# INTERPLACA.net
KiCad netlist of a schematic drawn in Altium Designer
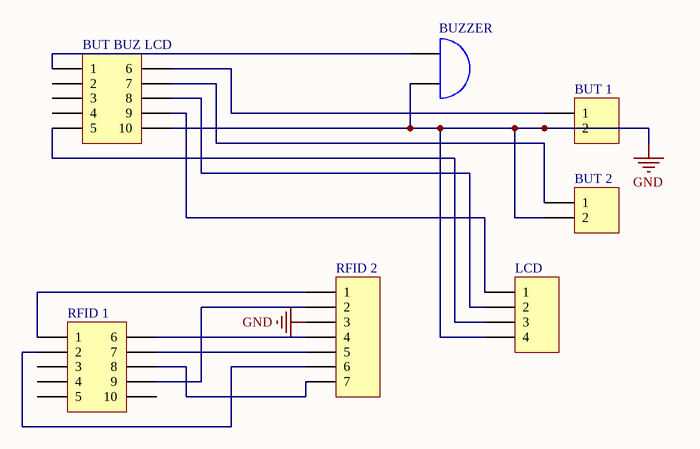
[diagram p0: INTERPLACA.SchDoc]

(export (version "E")
  (design (tool "Eeschema 10.0.6"))
  (components
    (comp (ref "BUT 1")
      (value "Header 2")
      (footprint "BORNERA 2 pin")
      (description "Header, 2-Pin")
      (fields (field (name "PUBLISHER") "Altium Limited"))
      (libsource (lib "Miscellaneous Connectors") (part "Header 2"))
    )
    (comp (ref "BUT 2")
      (value "Header 2")
      (footprint "BORNERA 2 pin")
      (description "Header, 2-Pin")
      (fields (field (name "PUBLISHER") "Altium Limited"))
      (libsource (lib "Miscellaneous Connectors") (part "Header 2"))
    )
    (comp (ref "BUT BUZ LCD")
      (value "Header 5X2A")
      (footprint "HDR2X5_CEN")
      (description "Header, 5-Pin, Dual row")
      (fields (field (name "PUBLISHER") "Altium Limited"))
      (libsource (lib "Miscellaneous Connectors") (part "Header 5X2A"))
    )
    (comp (ref "BUZZER")
      (value "Bell")
      (footprint "PIN2")
      (description "Electrical Bell")
      (fields (field (name "PUBLISHER") "Altium Limited"))
      (libsource (lib "Miscellaneous Devices") (part "Bell"))
    )
    (comp (ref "LCD")
      (value "Header 4")
      (footprint "HDR1X4")
      (description "Header, 4-Pin")
      (fields (field (name "PUBLISHER") "Altium Limited"))
      (libsource (lib "Miscellaneous Connectors") (part "Header 4"))
    )
    (comp (ref "RFID 1")
      (value "Header 5X2A")
      (footprint "HDR2X5_CEN")
      (description "Header, 5-Pin, Dual row")
      (fields (field (name "PUBLISHER") "Altium Limited"))
      (libsource (lib "Miscellaneous Connectors") (part "Header 5X2A"))
    )
    (comp (ref "RFID 2")
      (value "Header 7")
      (footprint "HDR1X7")
      (description "Header, 7-Pin")
      (fields (field (name "PUBLISHER") "Altium Limited"))
      (libsource (lib "Miscellaneous Connectors") (part "Header 7"))
    )
  )
  (nets
    (net (code "1") (name "GND") (class "Default")
      (node (ref "BUT 1") (pin "2") (pinfunction "2_2") (pintype "passive"))
      (node (ref "BUT 2") (pin "2") (pinfunction "2_2") (pintype "passive"))
      (node (ref "BUT BUZ LCD") (pin "10") (pinfunction "10_10") (pintype "passive"))
      (node (ref "BUZZER") (pin "2") (pinfunction "B_2") (pintype "passive"))
      (node (ref "LCD") (pin "4") (pinfunction "4_4") (pintype "passive"))
      (node (ref "RFID 2") (pin "3") (pinfunction "3_3") (pintype "passive"))
    )
    (net (code "2") (name "Net-(BUT 1-Pad1)") (class "Default")
      (node (ref "BUT 1") (pin "1") (pinfunction "1_1") (pintype "passive"))
      (node (ref "BUT BUZ LCD") (pin "6") (pinfunction "6_6") (pintype "passive"))
    )
    (net (code "3") (name "Net-(BUT 2-Pad1)") (class "Default")
      (node (ref "BUT 2") (pin "1") (pinfunction "1_1") (pintype "passive"))
      (node (ref "BUT BUZ LCD") (pin "7") (pinfunction "7_7") (pintype "passive"))
    )
    (net (code "4") (name "Net-(BUT BUZ LCD-Pad5)") (class "Default")
      (node (ref "BUT BUZ LCD") (pin "5") (pinfunction "5_5") (pintype "passive"))
      (node (ref "LCD") (pin "3") (pinfunction "3_3") (pintype "passive"))
    )
    (net (code "5") (name "Net-(BUT BUZ LCD-Pad8)") (class "Default")
      (node (ref "BUT BUZ LCD") (pin "8") (pinfunction "8_8") (pintype "passive"))
      (node (ref "LCD") (pin "2") (pinfunction "2_2") (pintype "passive"))
    )
    (net (code "6") (name "Net-(BUT BUZ LCD-Pad9)") (class "Default")
      (node (ref "BUT BUZ LCD") (pin "9") (pinfunction "9_9") (pintype "passive"))
      (node (ref "LCD") (pin "1") (pinfunction "1_1") (pintype "passive"))
    )
    (net (code "7") (name "Net-(BUZZER-A)") (class "Default")
      (node (ref "BUT BUZ LCD") (pin "1") (pinfunction "1_1") (pintype "passive"))
      (node (ref "BUZZER") (pin "1") (pinfunction "A_1") (pintype "passive"))
    )
    (net (code "8") (name "Net-(RFID 1-Pad1)") (class "Default")
      (node (ref "RFID 1") (pin "1") (pinfunction "1_1") (pintype "passive"))
      (node (ref "RFID 2") (pin "1") (pinfunction "1_1") (pintype "passive"))
    )
    (net (code "9") (name "Net-(RFID 1-Pad2)") (class "Default")
      (node (ref "RFID 1") (pin "2") (pinfunction "2_2") (pintype "passive"))
      (node (ref "RFID 2") (pin "6") (pinfunction "6_6") (pintype "passive"))
    )
    (net (code "10") (name "Net-(RFID 1-Pad6)") (class "Default")
      (node (ref "RFID 1") (pin "6") (pinfunction "6_6") (pintype "passive"))
      (node (ref "RFID 2") (pin "4") (pinfunction "4_4") (pintype "passive"))
    )
    (net (code "11") (name "Net-(RFID 1-Pad7)") (class "Default")
      (node (ref "RFID 1") (pin "7") (pinfunction "7_7") (pintype "passive"))
      (node (ref "RFID 2") (pin "5") (pinfunction "5_5") (pintype "passive"))
    )
    (net (code "12") (name "Net-(RFID 1-Pad8)") (class "Default")
      (node (ref "RFID 1") (pin "8") (pinfunction "8_8") (pintype "passive"))
      (node (ref "RFID 2") (pin "7") (pinfunction "7_7") (pintype "passive"))
    )
    (net (code "13") (name "Net-(RFID 1-Pad9)") (class "Default")
      (node (ref "RFID 1") (pin "9") (pinfunction "9_9") (pintype "passive"))
      (node (ref "RFID 2") (pin "2") (pinfunction "2_2") (pintype "passive"))
    )
    (net (code "14") (name "unconnected-(BUT BUZ LCD-Pad2)") (class "Default")
      (node (ref "BUT BUZ LCD") (pin "2") (pinfunction "2_2") (pintype "passive"))
    )
    (net (code "15") (name "unconnected-(BUT BUZ LCD-Pad3)") (class "Default")
      (node (ref "BUT BUZ LCD") (pin "3") (pinfunction "3_3") (pintype "passive"))
    )
    (net (code "16") (name "unconnected-(BUT BUZ LCD-Pad4)") (class "Default")
      (node (ref "BUT BUZ LCD") (pin "4") (pinfunction "4_4") (pintype "passive"))
    )
    (net (code "17") (name "unconnected-(RFID 1-Pad3)") (class "Default")
      (node (ref "RFID 1") (pin "3") (pinfunction "3_3") (pintype "passive"))
    )
    (net (code "18") (name "unconnected-(RFID 1-Pad4)") (class "Default")
      (node (ref "RFID 1") (pin "4") (pinfunction "4_4") (pintype "passive"))
    )
    (net (code "19") (name "unconnected-(RFID 1-Pad5)") (class "Default")
      (node (ref "RFID 1") (pin "5") (pinfunction "5_5") (pintype "passive"))
    )
    (net (code "20") (name "unconnected-(RFID 1-Pad10)") (class "Default")
      (node (ref "RFID 1") (pin "10") (pinfunction "10_10") (pintype "passive"))
    )
  )
)
